# Main_Sheet.net
KiCad netlist of a schematic drawn in Altium Designer
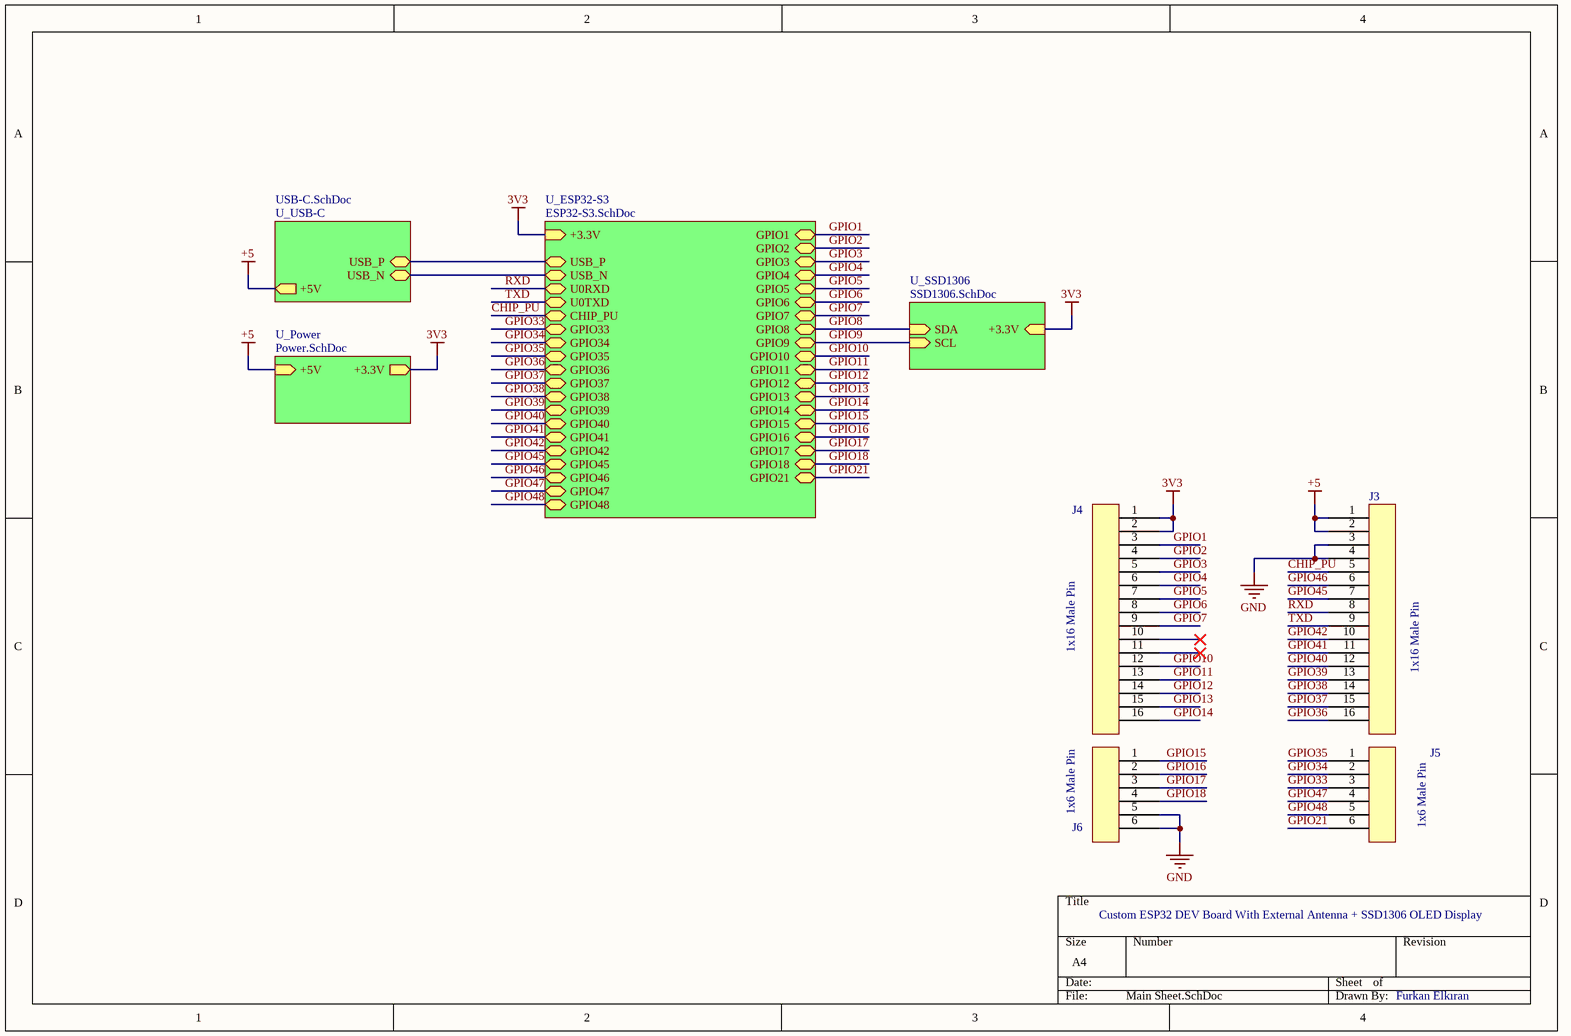
[diagram p0: Main Sheet.SchDoc]

(export (version "E")
  (design (tool "Eeschema 10.0.6"))
  (components
    (comp (ref "J3")
      (value "1x16 Male Pin")
      (footprint "1x16 Male Pin")
      (libsource (lib "Schlib1") (part "1x16 Male Pin"))
    )
    (comp (ref "J4")
      (value "1x16 Male Pin")
      (footprint "1x16 Male Pin")
      (libsource (lib "") (part "1x16 Male Pin_1"))
    )
    (comp (ref "J5")
      (value "1x6 Male Pin")
      (footprint "1x6 Male Pin")
      (libsource (lib "Schlib1") (part "1x6 Male Pin"))
    )
    (comp (ref "J6")
      (value "1x6 Male Pin")
      (footprint "1x6 Male Pin")
      (libsource (lib "") (part "1x6 Male Pin_1"))
    )
  )
  (nets
    (net (code "1") (name "+5") (class "Default")
      (node (ref "J3") (pin "1") (pinfunction "1_1") (pintype "passive"))
      (node (ref "J3") (pin "2") (pinfunction "2_2") (pintype "passive"))
    )
    (net (code "2") (name "/CHIP_PU") (class "Default")
      (node (ref "J3") (pin "5") (pinfunction "5_5") (pintype "passive"))
    )
    (net (code "3") (name "/GPIO1") (class "Default")
      (node (ref "J4") (pin "3") (pinfunction "3_3") (pintype "passive"))
    )
    (net (code "4") (name "/GPIO2") (class "Default")
      (node (ref "J4") (pin "4") (pinfunction "4_4") (pintype "passive"))
    )
    (net (code "5") (name "/GPIO3") (class "Default")
      (node (ref "J4") (pin "5") (pinfunction "5_5") (pintype "passive"))
    )
    (net (code "6") (name "/GPIO4") (class "Default")
      (node (ref "J4") (pin "6") (pinfunction "6_6") (pintype "passive"))
    )
    (net (code "7") (name "/GPIO5") (class "Default")
      (node (ref "J4") (pin "7") (pinfunction "7_7") (pintype "passive"))
    )
    (net (code "8") (name "/GPIO6") (class "Default")
      (node (ref "J4") (pin "8") (pinfunction "8_8") (pintype "passive"))
    )
    (net (code "9") (name "/GPIO7") (class "Default")
      (node (ref "J4") (pin "9") (pinfunction "9_9") (pintype "passive"))
    )
    (net (code "12") (name "/GPIO10") (class "Default")
      (node (ref "J4") (pin "12") (pinfunction "12_12") (pintype "passive"))
    )
    (net (code "13") (name "/GPIO11") (class "Default")
      (node (ref "J4") (pin "13") (pinfunction "13_13") (pintype "passive"))
    )
    (net (code "14") (name "/GPIO12") (class "Default")
      (node (ref "J4") (pin "14") (pinfunction "14_14") (pintype "passive"))
    )
    (net (code "15") (name "/GPIO13") (class "Default")
      (node (ref "J4") (pin "15") (pinfunction "15_15") (pintype "passive"))
    )
    (net (code "16") (name "/GPIO14") (class "Default")
      (node (ref "J4") (pin "16") (pinfunction "16_16") (pintype "passive"))
    )
    (net (code "17") (name "/GPIO15") (class "Default")
      (node (ref "J6") (pin "1") (pinfunction "1_1") (pintype "passive"))
    )
    (net (code "18") (name "/GPIO16") (class "Default")
      (node (ref "J6") (pin "2") (pinfunction "2_2") (pintype "passive"))
    )
    (net (code "19") (name "/GPIO17") (class "Default")
      (node (ref "J6") (pin "3") (pinfunction "3_3") (pintype "passive"))
    )
    (net (code "20") (name "/GPIO18") (class "Default")
      (node (ref "J6") (pin "4") (pinfunction "4_4") (pintype "passive"))
    )
    (net (code "21") (name "/GPIO21") (class "Default")
      (node (ref "J5") (pin "6") (pinfunction "6_6") (pintype "passive"))
    )
    (net (code "22") (name "/GPIO33") (class "Default")
      (node (ref "J5") (pin "3") (pinfunction "3_3") (pintype "passive"))
    )
    (net (code "23") (name "/GPIO34") (class "Default")
      (node (ref "J5") (pin "2") (pinfunction "2_2") (pintype "passive"))
    )
    (net (code "24") (name "/GPIO35") (class "Default")
      (node (ref "J5") (pin "1") (pinfunction "1_1") (pintype "passive"))
    )
    (net (code "25") (name "/GPIO36") (class "Default")
      (node (ref "J3") (pin "16") (pinfunction "16_16") (pintype "passive"))
    )
    (net (code "26") (name "/GPIO37") (class "Default")
      (node (ref "J3") (pin "15") (pinfunction "15_15") (pintype "passive"))
    )
    (net (code "27") (name "/GPIO38") (class "Default")
      (node (ref "J3") (pin "14") (pinfunction "14_14") (pintype "passive"))
    )
    (net (code "28") (name "/GPIO39") (class "Default")
      (node (ref "J3") (pin "13") (pinfunction "13_13") (pintype "passive"))
    )
    (net (code "29") (name "/GPIO40") (class "Default")
      (node (ref "J3") (pin "12") (pinfunction "12_12") (pintype "passive"))
    )
    (net (code "30") (name "/GPIO41") (class "Default")
      (node (ref "J3") (pin "11") (pinfunction "11_11") (pintype "passive"))
    )
    (net (code "31") (name "/GPIO42") (class "Default")
      (node (ref "J3") (pin "10") (pinfunction "10_10") (pintype "passive"))
    )
    (net (code "32") (name "/GPIO45") (class "Default")
      (node (ref "J3") (pin "7") (pinfunction "7_7") (pintype "passive"))
    )
    (net (code "33") (name "/GPIO46") (class "Default")
      (node (ref "J3") (pin "6") (pinfunction "6_6") (pintype "passive"))
    )
    (net (code "34") (name "/GPIO47") (class "Default")
      (node (ref "J5") (pin "4") (pinfunction "4_4") (pintype "passive"))
    )
    (net (code "35") (name "/GPIO48") (class "Default")
      (node (ref "J5") (pin "5") (pinfunction "5_5") (pintype "passive"))
    )
    (net (code "36") (name "/RXD") (class "Default")
      (node (ref "J3") (pin "8") (pinfunction "8_8") (pintype "passive"))
    )
    (net (code "37") (name "/TXD") (class "Default")
      (node (ref "J3") (pin "9") (pinfunction "9_9") (pintype "passive"))
    )
    (net (code "40") (name "3V3") (class "Default")
      (node (ref "J4") (pin "1") (pinfunction "1_1") (pintype "passive"))
      (node (ref "J4") (pin "2") (pinfunction "2_2") (pintype "passive"))
    )
    (net (code "41") (name "GND") (class "Default")
      (node (ref "J3") (pin "3") (pinfunction "3_3") (pintype "passive"))
      (node (ref "J3") (pin "4") (pinfunction "4_4") (pintype "passive"))
      (node (ref "J6") (pin "5") (pinfunction "5_5") (pintype "passive"))
      (node (ref "J6") (pin "6") (pinfunction "6_6") (pintype "passive"))
    )
    (net (code "42") (name "unconnected-(J4-Pad10)") (class "Default")
      (node (ref "J4") (pin "10") (pinfunction "10_10") (pintype "passive+no_connect"))
    )
    (net (code "43") (name "unconnected-(J4-Pad11)") (class "Default")
      (node (ref "J4") (pin "11") (pinfunction "11_11") (pintype "passive+no_connect"))
    )
  )
)
